# can-weichendecoder-servo.net
KiCad netlist of a schematic drawn in EAGLE
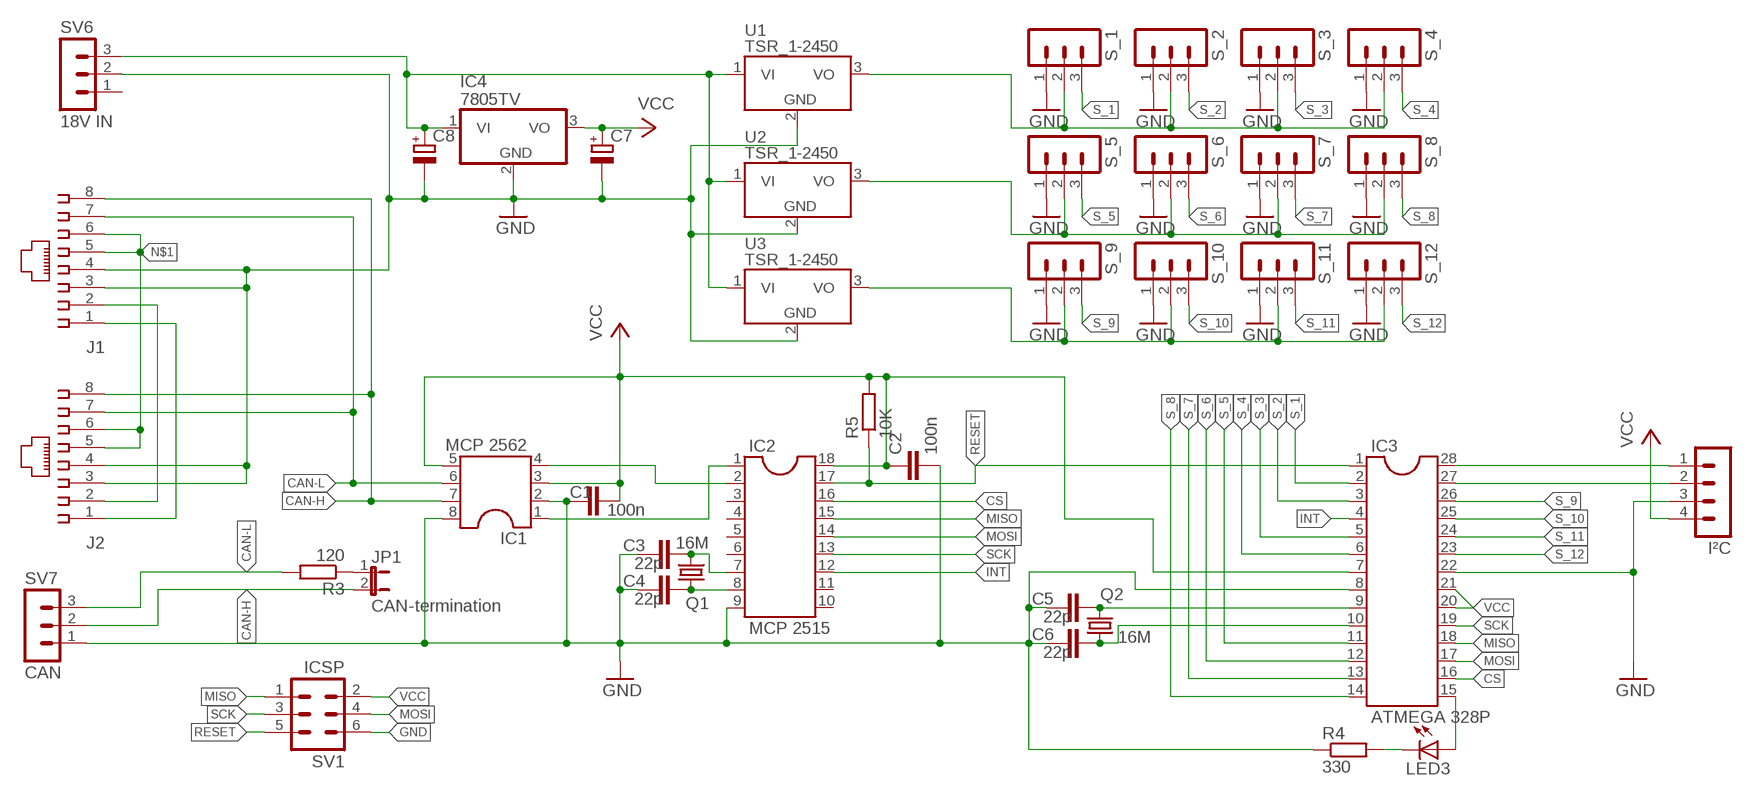
[diagram p0: schematic, sheet 1]

(export (version "E")
  (design (tool "Eeschema 10.0.6"))
  (components
    (comp (ref "C1")
      (value "100n")
      (footprint "eagle-import:C2.5-2")
      (libsource (lib "eagle-import") (part "C2.5/2"))
    )
    (comp (ref "C2")
      (value "100n")
      (footprint "eagle-import:C2.5-2")
      (libsource (lib "eagle-import") (part "C2.5/2"))
    )
    (comp (ref "C3")
      (value "22p")
      (footprint "eagle-import:C2.5-2")
      (libsource (lib "eagle-import") (part "C2.5/2"))
    )
    (comp (ref "C4")
      (value "22p")
      (footprint "eagle-import:C2.5-2")
      (libsource (lib "eagle-import") (part "C2.5/2"))
    )
    (comp (ref "C5")
      (value "22p")
      (footprint "eagle-import:C2.5-2")
      (libsource (lib "eagle-import") (part "C2.5/2"))
    )
    (comp (ref "C6")
      (value "22p")
      (footprint "eagle-import:C2.5-2")
      (libsource (lib "eagle-import") (part "C2.5/2"))
    )
    (comp (ref "C7")
      (value "CPOL-EUE2.5-6")
      (footprint "eagle-import:E2,5-6")
      (libsource (lib "eagle-import") (part "CPOL-EUE2.5-6"))
    )
    (comp (ref "C8")
      (value "CPOL-EUE2.5-6")
      (footprint "eagle-import:E2,5-6")
      (libsource (lib "eagle-import") (part "CPOL-EUE2.5-6"))
    )
    (comp (ref "IC1")
      (value "MCP 2562")
      (footprint "eagle-import:SOCKET-08")
      (libsource (lib "eagle-import") (part "DIL8S"))
    )
    (comp (ref "IC2")
      (value "MCP 2515")
      (footprint "eagle-import:SOCKET-18")
      (libsource (lib "eagle-import") (part "DIL18S"))
    )
    (comp (ref "IC3")
      (value "ATMEGA 328P")
      (footprint "eagle-import:DIL28-3")
      (libsource (lib "eagle-import") (part "DIL28-3"))
    )
    (comp (ref "IC4")
      (value "7805TV")
      (footprint "eagle-import:TO220V")
      (libsource (lib "eagle-import") (part "78TV05"))
    )
    (comp (ref "I²C")
      (value "MA04-1")
      (footprint "eagle-import:MA04-1")
      (libsource (lib "eagle-import") (part "MA04-1"))
    )
    (comp (ref "J1")
      (value "215877-7")
      (footprint "eagle-import:215877-7")
      (libsource (lib "eagle-import") (part "215877-7"))
    )
    (comp (ref "J2")
      (value "215877-7")
      (footprint "eagle-import:215877-7")
      (libsource (lib "eagle-import") (part "215877-7"))
    )
    (comp (ref "JP1")
      (value "CAN-termination")
      (footprint "eagle-import:JP1")
      (libsource (lib "eagle-import") (part "JP1E"))
    )
    (comp (ref "LED3")
      (value "LED5MM")
      (footprint "eagle-import:LED5MM")
      (libsource (lib "eagle-import") (part "LED5MM"))
    )
    (comp (ref "Q1")
      (value "16M")
      (footprint "eagle-import:HC49_S")
      (libsource (lib "eagle-import") (part "CRYSTALHC49S"))
    )
    (comp (ref "Q2")
      (value "16M")
      (footprint "eagle-import:HC49_S")
      (libsource (lib "eagle-import") (part "CRYSTALHC49S"))
    )
    (comp (ref "R3")
      (value "120")
      (footprint "eagle-import:0207_10")
      (libsource (lib "eagle-import") (part "R-EU_0207/10"))
    )
    (comp (ref "R4")
      (value "330")
      (footprint "eagle-import:0207_10")
      (libsource (lib "eagle-import") (part "R-EU_0207/10"))
    )
    (comp (ref "R5")
      (value "10K")
      (footprint "eagle-import:0207_10")
      (libsource (lib "eagle-import") (part "R-EU_0207/10"))
    )
    (comp (ref "SV1")
      (value "ICSP")
      (footprint "eagle-import:MA03-2")
      (libsource (lib "eagle-import") (part "MA03-2"))
    )
    (comp (ref "SV6")
      (value "18V IN")
      (footprint "eagle-import:MA03-1")
      (libsource (lib "eagle-import") (part "MA03-1"))
    )
    (comp (ref "SV7")
      (value "CAN")
      (footprint "eagle-import:MA03-1")
      (libsource (lib "eagle-import") (part "MA03-1"))
    )
    (comp (ref "S_1")
      (value "MA03-1")
      (footprint "eagle-import:MA03-1")
      (libsource (lib "eagle-import") (part "MA03-1"))
    )
    (comp (ref "S_2")
      (value "MA03-1")
      (footprint "eagle-import:MA03-1")
      (libsource (lib "eagle-import") (part "MA03-1"))
    )
    (comp (ref "S_3")
      (value "MA03-1")
      (footprint "eagle-import:MA03-1")
      (libsource (lib "eagle-import") (part "MA03-1"))
    )
    (comp (ref "S_4")
      (value "MA03-1")
      (footprint "eagle-import:MA03-1")
      (libsource (lib "eagle-import") (part "MA03-1"))
    )
    (comp (ref "S_5")
      (value "MA03-1")
      (footprint "eagle-import:MA03-1")
      (libsource (lib "eagle-import") (part "MA03-1"))
    )
    (comp (ref "S_6")
      (value "MA03-1")
      (footprint "eagle-import:MA03-1")
      (libsource (lib "eagle-import") (part "MA03-1"))
    )
    (comp (ref "S_7")
      (value "MA03-1")
      (footprint "eagle-import:MA03-1")
      (libsource (lib "eagle-import") (part "MA03-1"))
    )
    (comp (ref "S_8")
      (value "MA03-1")
      (footprint "eagle-import:MA03-1")
      (libsource (lib "eagle-import") (part "MA03-1"))
    )
    (comp (ref "S_9")
      (value "MA03-1")
      (footprint "eagle-import:MA03-1")
      (libsource (lib "eagle-import") (part "MA03-1"))
    )
    (comp (ref "S_10")
      (value "MA03-1")
      (footprint "eagle-import:MA03-1")
      (libsource (lib "eagle-import") (part "MA03-1"))
    )
    (comp (ref "S_11")
      (value "MA03-1")
      (footprint "eagle-import:MA03-1")
      (libsource (lib "eagle-import") (part "MA03-1"))
    )
    (comp (ref "S_12")
      (value "MA03-1")
      (footprint "eagle-import:MA03-1")
      (libsource (lib "eagle-import") (part "MA03-1"))
    )
    (comp (ref "U1")
      (value "TSR_1-2450")
      (footprint "eagle-import:TSR-1")
      (libsource (lib "eagle-import") (part "TSR_1-2450"))
    )
    (comp (ref "U2")
      (value "TSR_1-2450")
      (footprint "eagle-import:TSR-1")
      (libsource (lib "eagle-import") (part "TSR_1-2450"))
    )
    (comp (ref "U3")
      (value "TSR_1-2450")
      (footprint "eagle-import:TSR-1")
      (libsource (lib "eagle-import") (part "TSR_1-2450"))
    )
  )
  (nets
    (net (code "1") (name "CAN-H") (class "Default")
      (node (ref "IC1") (pin "7") (pinfunction "7_7") (pintype "passive"))
      (node (ref "J1") (pin "8") (pinfunction "8_8") (pintype "passive"))
      (node (ref "J2") (pin "8") (pinfunction "8_8") (pintype "passive"))
      (node (ref "JP1") (pin "2") (pinfunction "2_2") (pintype "passive"))
      (node (ref "SV7") (pin "2") (pinfunction "2_2") (pintype "passive"))
    )
    (net (code "2") (name "CAN-L") (class "Default")
      (node (ref "IC1") (pin "6") (pinfunction "6_6") (pintype "passive"))
      (node (ref "J1") (pin "7") (pinfunction "7_7") (pintype "passive"))
      (node (ref "J2") (pin "7") (pinfunction "7_7") (pintype "passive"))
      (node (ref "R3") (pin "2") (pinfunction "2_2") (pintype "passive"))
      (node (ref "SV7") (pin "3") (pinfunction "3_3") (pintype "passive"))
    )
    (net (code "3") (name "CS") (class "Default")
      (node (ref "IC2") (pin "16") (pinfunction "16_16") (pintype "passive"))
      (node (ref "IC3") (pin "16") (pinfunction "16_16") (pintype "passive"))
    )
    (net (code "4") (name "GND") (class "Default")
      (node (ref "C1") (pin "1") (pinfunction "1_1") (pintype "passive"))
      (node (ref "C2") (pin "2") (pinfunction "2_2") (pintype "passive"))
      (node (ref "C3") (pin "1") (pinfunction "1_1") (pintype "passive"))
      (node (ref "C4") (pin "1") (pinfunction "1_1") (pintype "passive"))
      (node (ref "C5") (pin "1") (pinfunction "1_1") (pintype "passive"))
      (node (ref "C6") (pin "1") (pinfunction "1_1") (pintype "passive"))
      (node (ref "C7") (pin "-") (pinfunction "-_-") (pintype "passive"))
      (node (ref "C8") (pin "-") (pinfunction "-_-") (pintype "passive"))
      (node (ref "IC1") (pin "2") (pinfunction "2_2") (pintype "passive"))
      (node (ref "IC1") (pin "8") (pinfunction "8_8") (pintype "passive"))
      (node (ref "IC2") (pin "9") (pinfunction "9_9") (pintype "passive"))
      (node (ref "IC3") (pin "22") (pinfunction "22_22") (pintype "passive"))
      (node (ref "IC3") (pin "8") (pinfunction "8_8") (pintype "passive"))
      (node (ref "IC4") (pin "2") (pinfunction "GND_2") (pintype "passive"))
      (node (ref "I²C") (pin "3") (pinfunction "3_3") (pintype "passive"))
      (node (ref "J1") (pin "3") (pinfunction "3_3") (pintype "passive"))
      (node (ref "J1") (pin "4") (pinfunction "4_4") (pintype "passive"))
      (node (ref "J2") (pin "3") (pinfunction "3_3") (pintype "passive"))
      (node (ref "J2") (pin "4") (pinfunction "4_4") (pintype "passive"))
      (node (ref "R4") (pin "1") (pinfunction "1_1") (pintype "passive"))
      (node (ref "SV1") (pin "6") (pinfunction "6_6") (pintype "passive"))
      (node (ref "SV6") (pin "2") (pinfunction "2_2") (pintype "passive"))
      (node (ref "SV7") (pin "1") (pinfunction "1_1") (pintype "passive"))
      (node (ref "S_1") (pin "1") (pinfunction "1_1") (pintype "passive"))
      (node (ref "S_10") (pin "1") (pinfunction "1_1") (pintype "passive"))
      (node (ref "S_11") (pin "1") (pinfunction "1_1") (pintype "passive"))
      (node (ref "S_12") (pin "1") (pinfunction "1_1") (pintype "passive"))
      (node (ref "S_2") (pin "1") (pinfunction "1_1") (pintype "passive"))
      (node (ref "S_3") (pin "1") (pinfunction "1_1") (pintype "passive"))
      (node (ref "S_4") (pin "1") (pinfunction "1_1") (pintype "passive"))
      (node (ref "S_5") (pin "1") (pinfunction "1_1") (pintype "passive"))
      (node (ref "S_6") (pin "1") (pinfunction "1_1") (pintype "passive"))
      (node (ref "S_7") (pin "1") (pinfunction "1_1") (pintype "passive"))
      (node (ref "S_8") (pin "1") (pinfunction "1_1") (pintype "passive"))
      (node (ref "S_9") (pin "1") (pinfunction "1_1") (pintype "passive"))
      (node (ref "U1") (pin "2") (pinfunction "GND_2") (pintype "power_in"))
      (node (ref "U2") (pin "2") (pinfunction "GND_2") (pintype "power_in"))
      (node (ref "U3") (pin "2") (pinfunction "GND_2") (pintype "power_in"))
    )
    (net (code "5") (name "INT") (class "Default")
      (node (ref "IC2") (pin "12") (pinfunction "12_12") (pintype "passive"))
      (node (ref "IC3") (pin "4") (pinfunction "4_4") (pintype "passive"))
    )
    (net (code "6") (name "MISO") (class "Default")
      (node (ref "IC2") (pin "15") (pinfunction "15_15") (pintype "passive"))
      (node (ref "IC3") (pin "18") (pinfunction "18_18") (pintype "passive"))
      (node (ref "SV1") (pin "1") (pinfunction "1_1") (pintype "passive"))
    )
    (net (code "7") (name "MOSI") (class "Default")
      (node (ref "IC2") (pin "14") (pinfunction "14_14") (pintype "passive"))
      (node (ref "IC3") (pin "17") (pinfunction "17_17") (pintype "passive"))
      (node (ref "SV1") (pin "4") (pinfunction "4_4") (pintype "passive"))
    )
    (net (code "8") (name "N$1") (class "Default")
      (node (ref "J1") (pin "5") (pinfunction "5_5") (pintype "passive"))
      (node (ref "J1") (pin "6") (pinfunction "6_6") (pintype "passive"))
      (node (ref "J2") (pin "5") (pinfunction "5_5") (pintype "passive"))
      (node (ref "J2") (pin "6") (pinfunction "6_6") (pintype "passive"))
    )
    (net (code "9") (name "Net-(C3-Pad2)") (class "Default")
      (node (ref "C3") (pin "2") (pinfunction "2_2") (pintype "passive"))
      (node (ref "IC2") (pin "7") (pinfunction "7_7") (pintype "passive"))
      (node (ref "Q1") (pin "2") (pinfunction "2_2") (pintype "passive"))
    )
    (net (code "10") (name "Net-(C4-Pad2)") (class "Default")
      (node (ref "C4") (pin "2") (pinfunction "2_2") (pintype "passive"))
      (node (ref "IC2") (pin "8") (pinfunction "8_8") (pintype "passive"))
      (node (ref "Q1") (pin "1") (pinfunction "1_1") (pintype "passive"))
    )
    (net (code "11") (name "Net-(C5-Pad2)") (class "Default")
      (node (ref "C5") (pin "2") (pinfunction "2_2") (pintype "passive"))
      (node (ref "IC3") (pin "9") (pinfunction "9_9") (pintype "passive"))
      (node (ref "Q2") (pin "2") (pinfunction "2_2") (pintype "passive"))
    )
    (net (code "12") (name "Net-(C6-Pad2)") (class "Default")
      (node (ref "C6") (pin "2") (pinfunction "2_2") (pintype "passive"))
      (node (ref "IC3") (pin "10") (pinfunction "10_10") (pintype "passive"))
      (node (ref "Q2") (pin "1") (pinfunction "1_1") (pintype "passive"))
    )
    (net (code "13") (name "Net-(IC1-Pad1)") (class "Default")
      (node (ref "IC1") (pin "1") (pinfunction "1_1") (pintype "passive"))
      (node (ref "IC2") (pin "1") (pinfunction "1_1") (pintype "passive"))
    )
    (net (code "14") (name "Net-(IC1-Pad4)") (class "Default")
      (node (ref "IC1") (pin "4") (pinfunction "4_4") (pintype "passive"))
      (node (ref "IC2") (pin "2") (pinfunction "2_2") (pintype "passive"))
    )
    (net (code "15") (name "Net-(IC3-Pad15)") (class "Default")
      (node (ref "IC3") (pin "15") (pinfunction "15_15") (pintype "passive"))
      (node (ref "LED3") (pin "A") (pinfunction "A_A") (pintype "passive"))
    )
    (net (code "16") (name "Net-(IC3-Pad27)") (class "Default")
      (node (ref "IC3") (pin "27") (pinfunction "27_27") (pintype "passive"))
      (node (ref "I²C") (pin "2") (pinfunction "2_2") (pintype "passive"))
    )
    (net (code "17") (name "Net-(IC3-Pad28)") (class "Default")
      (node (ref "IC3") (pin "28") (pinfunction "28_28") (pintype "passive"))
      (node (ref "I²C") (pin "1") (pinfunction "1_1") (pintype "passive"))
    )
    (net (code "18") (name "Net-(IC4-VI)") (class "Default")
      (node (ref "C8") (pin "+") (pinfunction "+_+") (pintype "passive"))
      (node (ref "IC4") (pin "1") (pinfunction "VI_1") (pintype "input"))
      (node (ref "SV6") (pin "3") (pinfunction "3_3") (pintype "passive"))
      (node (ref "U1") (pin "1") (pinfunction "VI_1") (pintype "power_in"))
      (node (ref "U2") (pin "1") (pinfunction "VI_1") (pintype "power_in"))
      (node (ref "U3") (pin "1") (pinfunction "VI_1") (pintype "power_in"))
    )
    (net (code "19") (name "Net-(J1-Pad1)") (class "Default")
      (node (ref "J1") (pin "1") (pinfunction "1_1") (pintype "passive"))
      (node (ref "J2") (pin "1") (pinfunction "1_1") (pintype "passive"))
    )
    (net (code "20") (name "Net-(J1-Pad2)") (class "Default")
      (node (ref "J1") (pin "2") (pinfunction "2_2") (pintype "passive"))
      (node (ref "J2") (pin "2") (pinfunction "2_2") (pintype "passive"))
    )
    (net (code "21") (name "Net-(JP1-Pad1)") (class "Default")
      (node (ref "JP1") (pin "1") (pinfunction "1_1") (pintype "passive"))
      (node (ref "R3") (pin "1") (pinfunction "1_1") (pintype "passive"))
    )
    (net (code "22") (name "Net-(LED3-C)") (class "Default")
      (node (ref "LED3") (pin "K") (pinfunction "C_K") (pintype "passive"))
      (node (ref "R4") (pin "2") (pinfunction "2_2") (pintype "passive"))
    )
    (net (code "23") (name "Net-(U1-VO)") (class "Default")
      (node (ref "S_1") (pin "2") (pinfunction "2_2") (pintype "passive"))
      (node (ref "S_2") (pin "2") (pinfunction "2_2") (pintype "passive"))
      (node (ref "S_3") (pin "2") (pinfunction "2_2") (pintype "passive"))
      (node (ref "S_4") (pin "2") (pinfunction "2_2") (pintype "passive"))
      (node (ref "U1") (pin "3") (pinfunction "VO_3") (pintype "power_in"))
    )
    (net (code "24") (name "Net-(U2-VO)") (class "Default")
      (node (ref "S_5") (pin "2") (pinfunction "2_2") (pintype "passive"))
      (node (ref "S_6") (pin "2") (pinfunction "2_2") (pintype "passive"))
      (node (ref "S_7") (pin "2") (pinfunction "2_2") (pintype "passive"))
      (node (ref "S_8") (pin "2") (pinfunction "2_2") (pintype "passive"))
      (node (ref "U2") (pin "3") (pinfunction "VO_3") (pintype "power_in"))
    )
    (net (code "25") (name "Net-(U3-VO)") (class "Default")
      (node (ref "S_10") (pin "2") (pinfunction "2_2") (pintype "passive"))
      (node (ref "S_11") (pin "2") (pinfunction "2_2") (pintype "passive"))
      (node (ref "S_12") (pin "2") (pinfunction "2_2") (pintype "passive"))
      (node (ref "S_9") (pin "2") (pinfunction "2_2") (pintype "passive"))
      (node (ref "U3") (pin "3") (pinfunction "VO_3") (pintype "power_in"))
    )
    (net (code "26") (name "RESET") (class "Default")
      (node (ref "IC2") (pin "17") (pinfunction "17_17") (pintype "passive"))
      (node (ref "IC3") (pin "1") (pinfunction "1_1") (pintype "passive"))
      (node (ref "R5") (pin "1") (pinfunction "1_1") (pintype "passive"))
      (node (ref "SV1") (pin "5") (pinfunction "5_5") (pintype "passive"))
    )
    (net (code "27") (name "SCK") (class "Default")
      (node (ref "IC2") (pin "13") (pinfunction "13_13") (pintype "passive"))
      (node (ref "IC3") (pin "19") (pinfunction "19_19") (pintype "passive"))
      (node (ref "SV1") (pin "3") (pinfunction "3_3") (pintype "passive"))
    )
    (net (code "28") (name "S_1") (class "Default")
      (node (ref "IC3") (pin "2") (pinfunction "2_2") (pintype "passive"))
      (node (ref "S_1") (pin "3") (pinfunction "3_3") (pintype "passive"))
    )
    (net (code "29") (name "S_2") (class "Default")
      (node (ref "IC3") (pin "3") (pinfunction "3_3") (pintype "passive"))
      (node (ref "S_2") (pin "3") (pinfunction "3_3") (pintype "passive"))
    )
    (net (code "30") (name "S_3") (class "Default")
      (node (ref "IC3") (pin "5") (pinfunction "5_5") (pintype "passive"))
      (node (ref "S_3") (pin "3") (pinfunction "3_3") (pintype "passive"))
    )
    (net (code "31") (name "S_4") (class "Default")
      (node (ref "IC3") (pin "6") (pinfunction "6_6") (pintype "passive"))
      (node (ref "S_4") (pin "3") (pinfunction "3_3") (pintype "passive"))
    )
    (net (code "32") (name "S_5") (class "Default")
      (node (ref "IC3") (pin "11") (pinfunction "11_11") (pintype "passive"))
      (node (ref "S_5") (pin "3") (pinfunction "3_3") (pintype "passive"))
    )
    (net (code "33") (name "S_6") (class "Default")
      (node (ref "IC3") (pin "12") (pinfunction "12_12") (pintype "passive"))
      (node (ref "S_6") (pin "3") (pinfunction "3_3") (pintype "passive"))
    )
    (net (code "34") (name "S_7") (class "Default")
      (node (ref "IC3") (pin "13") (pinfunction "13_13") (pintype "passive"))
      (node (ref "S_7") (pin "3") (pinfunction "3_3") (pintype "passive"))
    )
    (net (code "35") (name "S_8") (class "Default")
      (node (ref "IC3") (pin "14") (pinfunction "14_14") (pintype "passive"))
      (node (ref "S_8") (pin "3") (pinfunction "3_3") (pintype "passive"))
    )
    (net (code "36") (name "S_9") (class "Default")
      (node (ref "IC3") (pin "26") (pinfunction "26_26") (pintype "passive"))
      (node (ref "S_9") (pin "3") (pinfunction "3_3") (pintype "passive"))
    )
    (net (code "37") (name "S_10") (class "Default")
      (node (ref "IC3") (pin "25") (pinfunction "25_25") (pintype "passive"))
      (node (ref "S_10") (pin "3") (pinfunction "3_3") (pintype "passive"))
    )
    (net (code "38") (name "S_11") (class "Default")
      (node (ref "IC3") (pin "24") (pinfunction "24_24") (pintype "passive"))
      (node (ref "S_11") (pin "3") (pinfunction "3_3") (pintype "passive"))
    )
    (net (code "39") (name "S_12") (class "Default")
      (node (ref "IC3") (pin "23") (pinfunction "23_23") (pintype "passive"))
      (node (ref "S_12") (pin "3") (pinfunction "3_3") (pintype "passive"))
    )
    (net (code "40") (name "VCC") (class "Default")
      (node (ref "C1") (pin "2") (pinfunction "2_2") (pintype "passive"))
      (node (ref "C2") (pin "1") (pinfunction "1_1") (pintype "passive"))
      (node (ref "C7") (pin "+") (pinfunction "+_+") (pintype "passive"))
      (node (ref "IC1") (pin "3") (pinfunction "3_3") (pintype "passive"))
      (node (ref "IC1") (pin "5") (pinfunction "5_5") (pintype "passive"))
      (node (ref "IC2") (pin "18") (pinfunction "18_18") (pintype "passive"))
      (node (ref "IC3") (pin "20") (pinfunction "20_20") (pintype "passive"))
      (node (ref "IC3") (pin "21") (pinfunction "21_21") (pintype "passive"))
      (node (ref "IC3") (pin "7") (pinfunction "7_7") (pintype "passive"))
      (node (ref "IC4") (pin "3") (pinfunction "VO_3") (pintype "passive"))
      (node (ref "I²C") (pin "4") (pinfunction "4_4") (pintype "passive"))
      (node (ref "R5") (pin "2") (pinfunction "2_2") (pintype "passive"))
      (node (ref "SV1") (pin "2") (pinfunction "2_2") (pintype "passive"))
    )
    (net (code "41") (name "unconnected-(IC2-Pad3)") (class "Default")
      (node (ref "IC2") (pin "3") (pinfunction "3_3") (pintype "passive"))
    )
    (net (code "42") (name "unconnected-(IC2-Pad4)") (class "Default")
      (node (ref "IC2") (pin "4") (pinfunction "4_4") (pintype "passive"))
    )
    (net (code "43") (name "unconnected-(IC2-Pad5)") (class "Default")
      (node (ref "IC2") (pin "5") (pinfunction "5_5") (pintype "passive"))
    )
    (net (code "44") (name "unconnected-(IC2-Pad6)") (class "Default")
      (node (ref "IC2") (pin "6") (pinfunction "6_6") (pintype "passive"))
    )
    (net (code "45") (name "unconnected-(IC2-Pad10)") (class "Default")
      (node (ref "IC2") (pin "10") (pinfunction "10_10") (pintype "passive"))
    )
    (net (code "46") (name "unconnected-(IC2-Pad11)") (class "Default")
      (node (ref "IC2") (pin "11") (pinfunction "11_11") (pintype "passive"))
    )
    (net (code "47") (name "unconnected-(SV6-Pad1)") (class "Default")
      (node (ref "SV6") (pin "1") (pinfunction "1_1") (pintype "passive"))
    )
  )
)
